# p2x3p-001.net
KiCad netlist of a schematic drawn in EAGLE
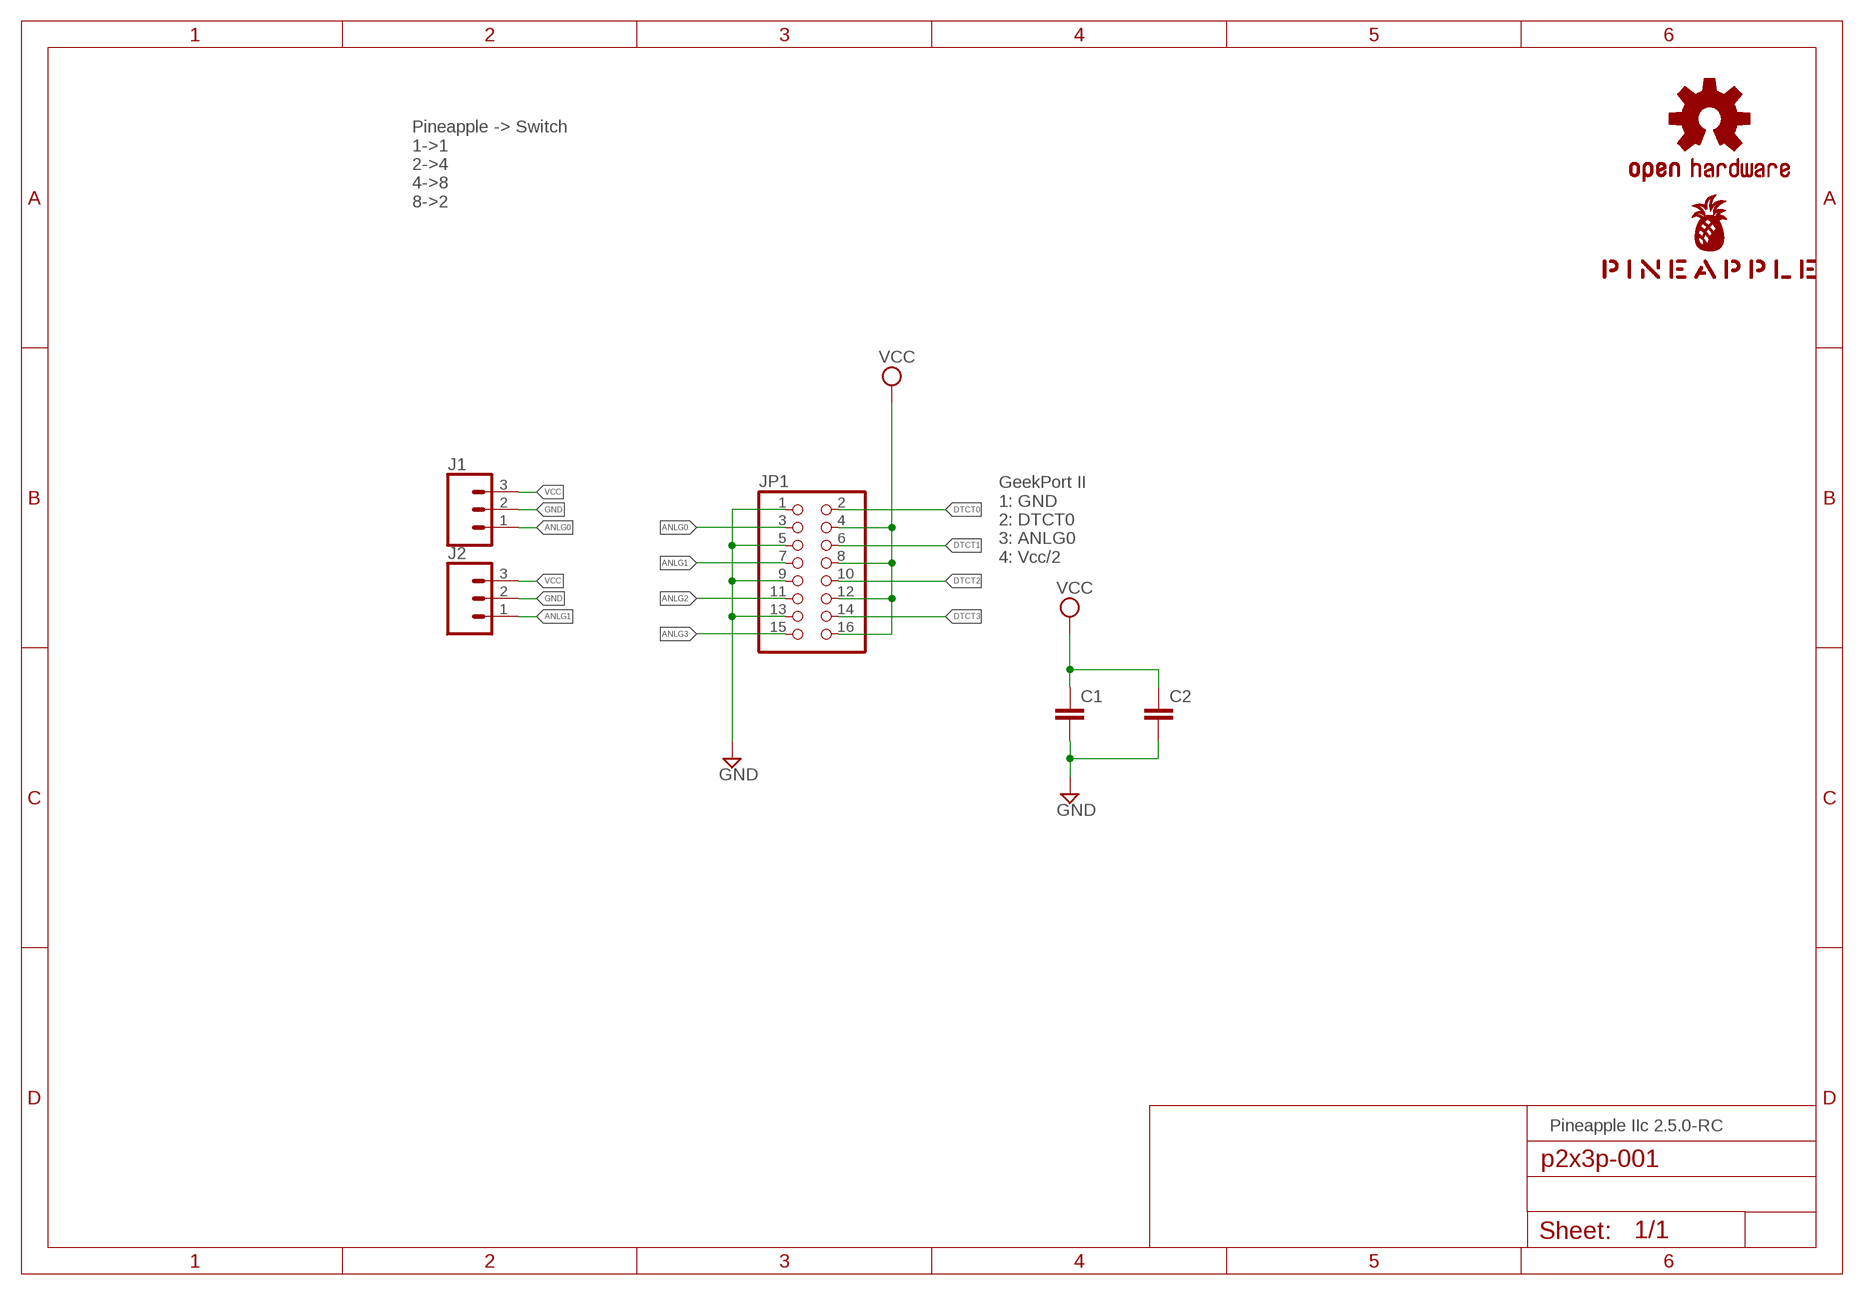
[diagram p0: schematic, sheet 1]

(export (version "E")
  (design (tool "Eeschema 10.0.6"))
  (components
    (comp (ref "C1")
      (value "C-EU025-024X044")
      (footprint "eagle-import:C025-024X044")
      (libsource (lib "eagle-import") (part "C-EU025-024X044"))
    )
    (comp (ref "C2")
      (value "C-EU025-024X044")
      (footprint "eagle-import:C025-024X044")
      (libsource (lib "eagle-import") (part "C-EU025-024X044"))
    )
    (comp (ref "J1")
      (value "CONN_03JST-PTH")
      (footprint "eagle-import:JST-3-PTH")
      (libsource (lib "eagle-import") (part "CONN_03JST-PTH"))
    )
    (comp (ref "J2")
      (value "CONN_03JST-PTH")
      (footprint "eagle-import:JST-3-PTH")
      (libsource (lib "eagle-import") (part "CONN_03JST-PTH"))
    )
    (comp (ref "JP1")
      (value "PINHD-2X8")
      (footprint "eagle-import:2X08")
      (libsource (lib "eagle-import") (part "PINHD-2X8"))
    )
    (comp (ref "LOGO1")
      (value "OSHW-LOGOS-COPPER")
      (footprint "eagle-import:OSHW-LOGO-S_COPPER")
      (libsource (lib "eagle-import") (part "OSHW-LOGOS-COPPER"))
    )
    (comp (ref "U$1")
      (value "PINEAPPLE450_SILK")
      (footprint "eagle-import:PINEAPPLE450_SILK")
      (libsource (lib "eagle-import") (part "PINEAPPLE450_SILK"))
    )
  )
  (nets
    (net (code "1") (name "ANLG0") (class "Default")
      (node (ref "J1") (pin "1") (pinfunction "1_1") (pintype "passive"))
      (node (ref "JP1") (pin "3") (pinfunction "3_3") (pintype "passive"))
    )
    (net (code "2") (name "ANLG1") (class "Default")
      (node (ref "J2") (pin "1") (pinfunction "1_1") (pintype "passive"))
      (node (ref "JP1") (pin "7") (pinfunction "7_7") (pintype "passive"))
    )
    (net (code "3") (name "ANLG2") (class "Default")
      (node (ref "JP1") (pin "11") (pinfunction "11_11") (pintype "passive"))
    )
    (net (code "4") (name "ANLG3") (class "Default")
      (node (ref "JP1") (pin "15") (pinfunction "15_15") (pintype "passive"))
    )
    (net (code "5") (name "DTCT0") (class "Default")
      (node (ref "JP1") (pin "2") (pinfunction "2_2") (pintype "passive"))
    )
    (net (code "6") (name "DTCT1") (class "Default")
      (node (ref "JP1") (pin "6") (pinfunction "6_6") (pintype "passive"))
    )
    (net (code "7") (name "DTCT2") (class "Default")
      (node (ref "JP1") (pin "10") (pinfunction "10_10") (pintype "passive"))
    )
    (net (code "8") (name "DTCT3") (class "Default")
      (node (ref "JP1") (pin "14") (pinfunction "14_14") (pintype "passive"))
    )
    (net (code "9") (name "GND") (class "Default")
      (node (ref "C1") (pin "2") (pinfunction "2_2") (pintype "passive"))
      (node (ref "C2") (pin "2") (pinfunction "2_2") (pintype "passive"))
      (node (ref "J1") (pin "2") (pinfunction "2_2") (pintype "passive"))
      (node (ref "J2") (pin "2") (pinfunction "2_2") (pintype "passive"))
      (node (ref "JP1") (pin "1") (pinfunction "1_1") (pintype "passive"))
      (node (ref "JP1") (pin "13") (pinfunction "13_13") (pintype "passive"))
      (node (ref "JP1") (pin "5") (pinfunction "5_5") (pintype "passive"))
      (node (ref "JP1") (pin "9") (pinfunction "9_9") (pintype "passive"))
    )
    (net (code "10") (name "VCC") (class "Default")
      (node (ref "C1") (pin "1") (pinfunction "1_1") (pintype "passive"))
      (node (ref "C2") (pin "1") (pinfunction "1_1") (pintype "passive"))
      (node (ref "J1") (pin "3") (pinfunction "3_3") (pintype "passive"))
      (node (ref "J2") (pin "3") (pinfunction "3_3") (pintype "passive"))
      (node (ref "JP1") (pin "12") (pinfunction "12_12") (pintype "passive"))
      (node (ref "JP1") (pin "16") (pinfunction "16_16") (pintype "passive"))
      (node (ref "JP1") (pin "4") (pinfunction "4_4") (pintype "passive"))
      (node (ref "JP1") (pin "8") (pinfunction "8_8") (pintype "passive"))
    )
  )
)
